# SAMV71_Xplained_Ultra_Memory.net
KiCad netlist of a schematic drawn in Altium Designer
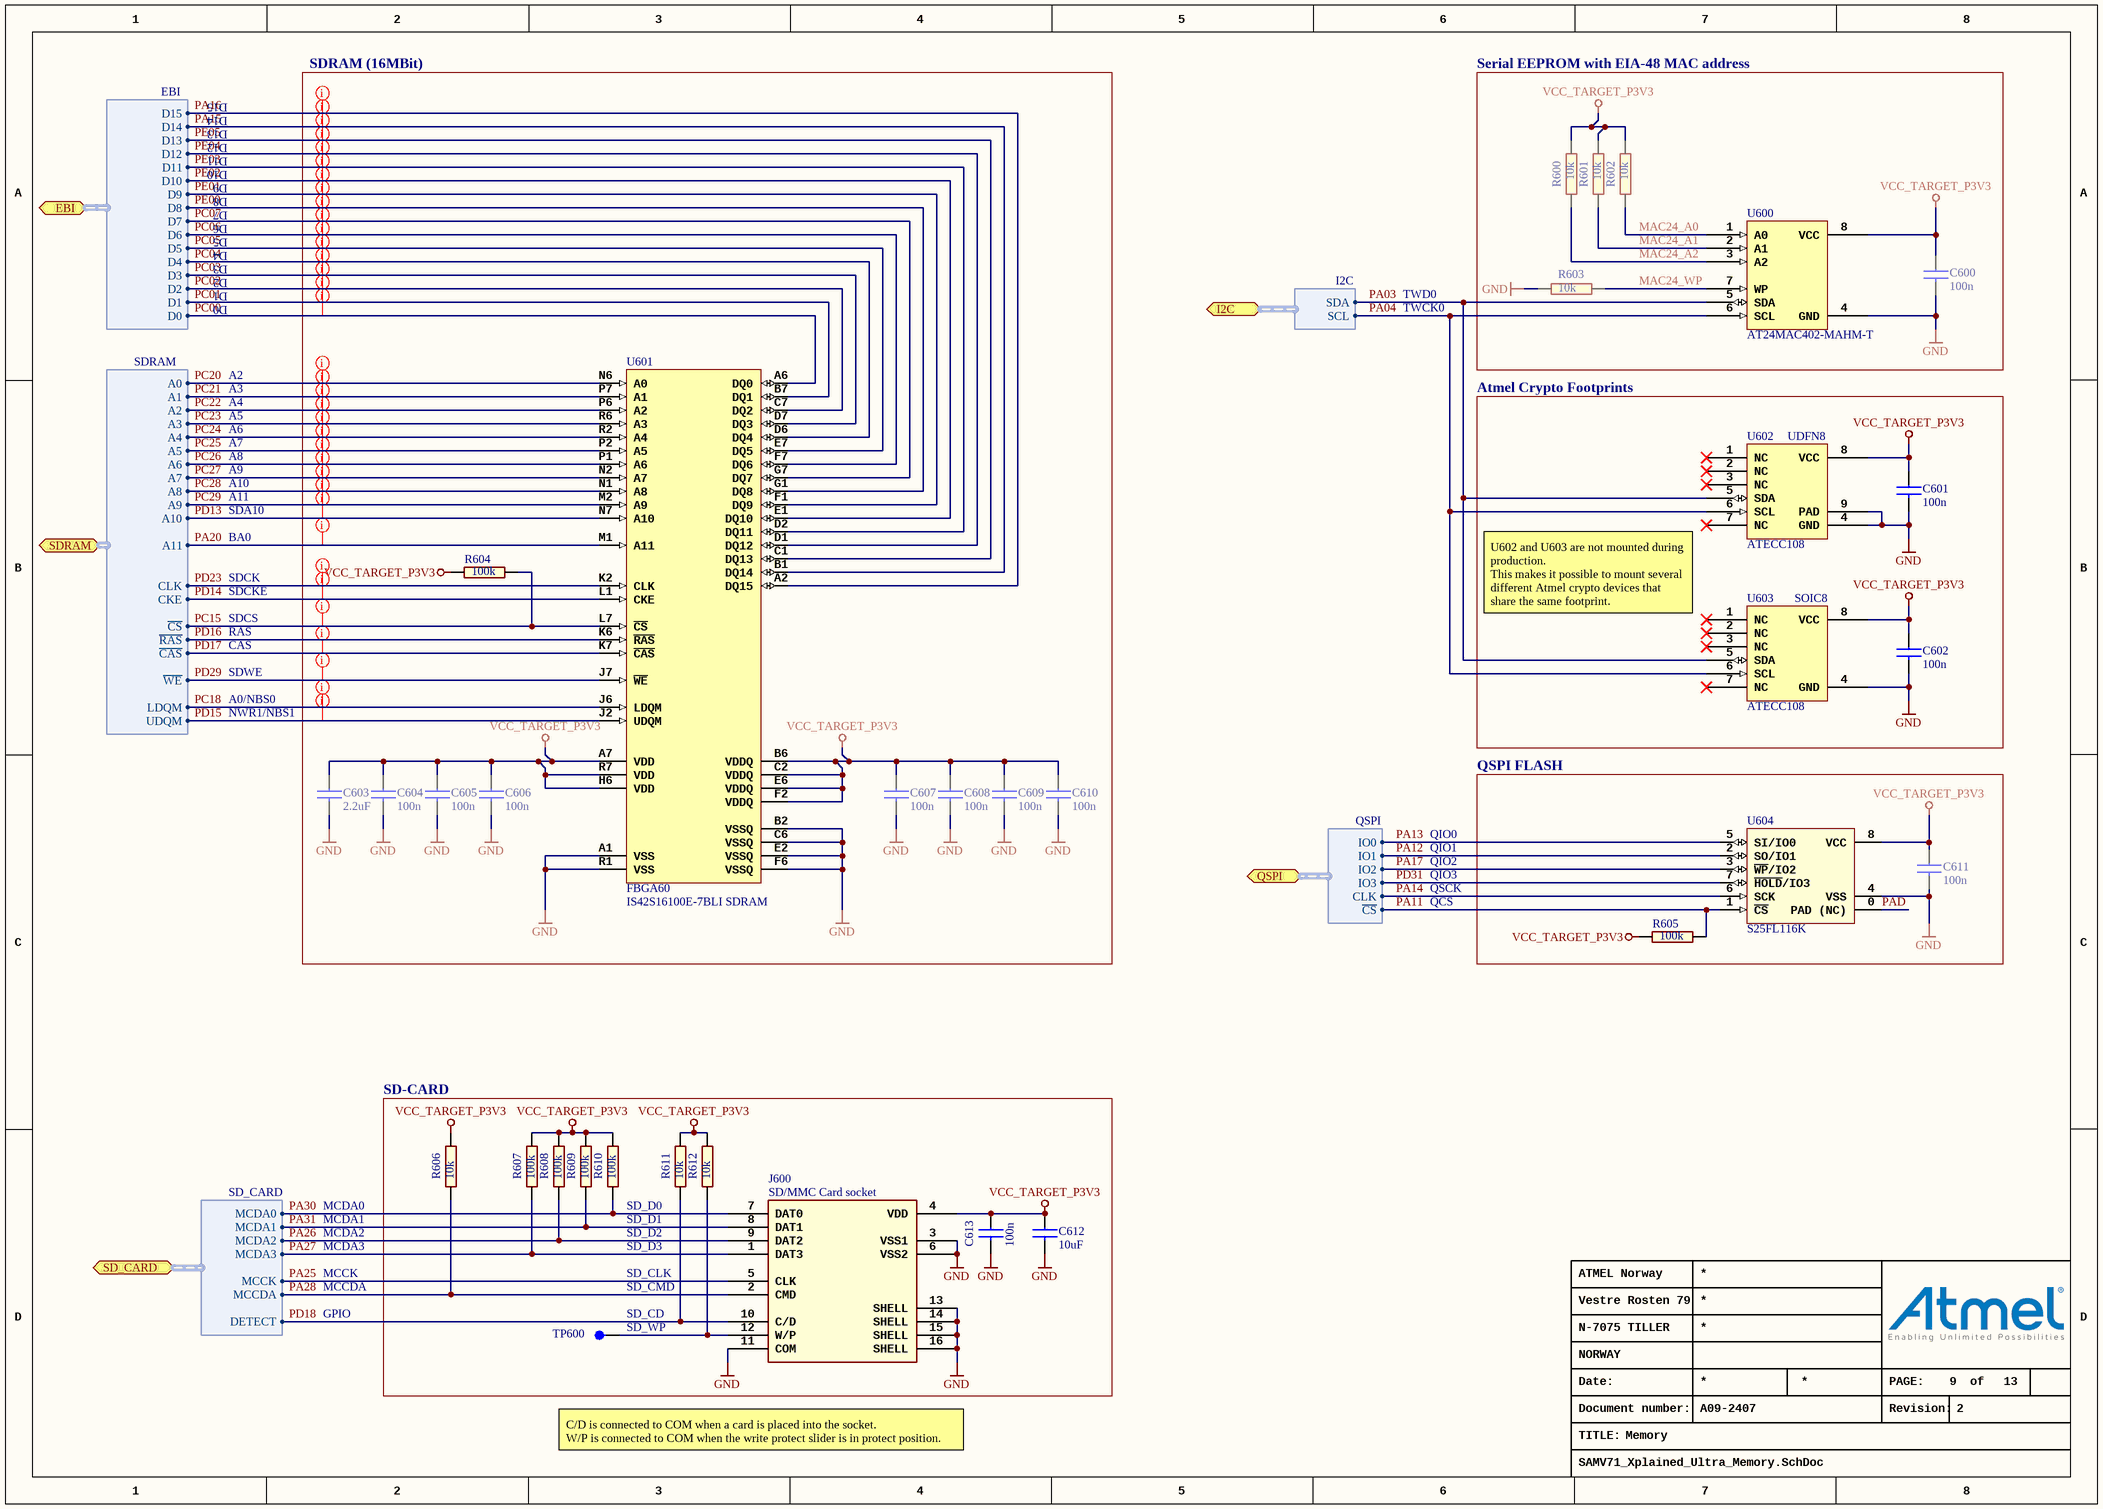
[diagram p0: SAMV71_Xplained_Ultra_Memory.SchDoc]

(export (version "E")
  (design (tool "Eeschema 10.0.6"))
  (components
    (comp (ref "C600")
      (value "100n")
      (footprint "AP1-00001")
      (description "Ceramic capacitor, SMD 0402, X7R, 16V, +/-10%")
      (fields (field (name "TOLERANCE") "16V, +/-10%") (field (name "MANUFACTURER") "Kemet"))
      (libsource (lib "AltiumDbLib") (part "CAP-NONPOL"))
    )
    (comp (ref "C601")
      (value "100n")
      (footprint "AP1-00001")
      (description "Ceramic capacitor, SMD 0402, X7R, 16V, +/-10%")
      (fields (field (name "TOLERANCE") "16V, +/-10%") (field (name "MANUFACTURER") "Kemet"))
      (libsource (lib "AltiumDbLib") (part "CAP-NONPOL"))
    )
    (comp (ref "C602")
      (value "100n")
      (footprint "AP1-00001")
      (description "Ceramic capacitor, SMD 0402, X7R, 16V, +/-10%")
      (fields (field (name "TOLERANCE") "16V, +/-10%") (field (name "MANUFACTURER") "Kemet"))
      (libsource (lib "AltiumDbLib") (part "CAP-NONPOL"))
    )
    (comp (ref "C603")
      (value "2.2uF")
      (footprint "AP1-00053")
      (description "Ceramic capacitor, SMD 0402, X5R, 6.3V, +/-20%")
      (fields (field (name "TOLERANCE") "Â±20%") (field (name "MANUFACTURER") "Kemet"))
      (libsource (lib "AltiumDbLib") (part "CAP-NONPOL"))
    )
    (comp (ref "C604")
      (value "100n")
      (footprint "AP1-00053")
      (description "Ceramic capacitor, SMD 0402, X7R, 16V, +/-10%")
      (fields (field (name "TOLERANCE") "16V, +/-10%") (field (name "MANUFACTURER") "Kemet"))
      (libsource (lib "AltiumDbLib") (part "CAP-NONPOL"))
    )
    (comp (ref "C605")
      (value "100n")
      (footprint "AP1-00053")
      (description "Ceramic capacitor, SMD 0402, X7R, 16V, +/-10%")
      (fields (field (name "TOLERANCE") "16V, +/-10%") (field (name "MANUFACTURER") "Kemet"))
      (libsource (lib "AltiumDbLib") (part "CAP-NONPOL"))
    )
    (comp (ref "C606")
      (value "100n")
      (footprint "AP1-00053")
      (description "Ceramic capacitor, SMD 0402, X7R, 16V, +/-10%")
      (fields (field (name "TOLERANCE") "16V, +/-10%") (field (name "MANUFACTURER") "Kemet"))
      (libsource (lib "AltiumDbLib") (part "CAP-NONPOL"))
    )
    (comp (ref "C607")
      (value "100n")
      (footprint "AP1-00053")
      (description "Ceramic capacitor, SMD 0402, X7R, 16V, +/-10%")
      (fields (field (name "TOLERANCE") "16V, +/-10%") (field (name "MANUFACTURER") "Kemet"))
      (libsource (lib "AltiumDbLib") (part "CAP-NONPOL"))
    )
    (comp (ref "C608")
      (value "100n")
      (footprint "AP1-00053")
      (description "Ceramic capacitor, SMD 0402, X7R, 16V, +/-10%")
      (fields (field (name "TOLERANCE") "16V, +/-10%") (field (name "MANUFACTURER") "Kemet"))
      (libsource (lib "AltiumDbLib") (part "CAP-NONPOL"))
    )
    (comp (ref "C609")
      (value "100n")
      (footprint "AP1-00053")
      (description "Ceramic capacitor, SMD 0402, X7R, 16V, +/-10%")
      (fields (field (name "TOLERANCE") "16V, +/-10%") (field (name "MANUFACTURER") "Kemet"))
      (libsource (lib "AltiumDbLib") (part "CAP-NONPOL"))
    )
    (comp (ref "C610")
      (value "100n")
      (footprint "AP1-00053")
      (description "Ceramic capacitor, SMD 0402, X7R, 16V, +/-10%")
      (fields (field (name "TOLERANCE") "16V, +/-10%") (field (name "MANUFACTURER") "Kemet"))
      (libsource (lib "AltiumDbLib") (part "CAP-NONPOL"))
    )
    (comp (ref "C611")
      (value "100n")
      (footprint "AP1-00001")
      (description "Ceramic capacitor, SMD 0402, X7R, 16V, +/-10%")
      (fields (field (name "TOLERANCE") "16V, +/-10%") (field (name "MANUFACTURER") "Kemet"))
      (libsource (lib "AltiumDbLib") (part "CAP-NONPOL"))
    )
    (comp (ref "C612")
      (value "10uF")
      (footprint "AP1-00041")
      (description "Ceramic capacitor, SMD 0805, X5R, 10V, 10 %, (de19441)")
      (fields (field (name "TOLERANCE") "10%") (field (name "MANUFACTURER") "Murata"))
      (libsource (lib "AltiumDbLib") (part "CAP-NONPOL"))
    )
    (comp (ref "C613")
      (value "100n")
      (footprint "AP1-00001")
      (description "Ceramic capacitor, SMD 0402, X7R, 16V, +/-10%")
      (fields (field (name "TOLERANCE") "16V, +/-10%") (field (name "MANUFACTURER") "Kemet"))
      (libsource (lib "AltiumDbLib") (part "CAP-NONPOL"))
    )
    (comp (ref "J600")
      (value "SD/MMC Card socket")
      (footprint "AP8-00377")
      (description "SD/MMC socket, 2.7mm, push-push, SMD")
      (fields
        (field (name "MANUFACTURER") "Kyocera-elco")
        (field (name "MPN") "KYOCERA - 14 5738 009 220 859+")
      )
      (libsource (lib "AltiumDbLib") (part "SD_MMC"))
    )
    (comp (ref "R600")
      (value "10k")
      (footprint "AP2-00000")
      (description "Thick film resistor, SMD 0402, 1/16W, 1%")
      (fields (field (name "TOLERANCE") "1 %") (field (name "MANUFACTURER") "vishay"))
      (libsource (lib "AltiumDbLib") (part "R2"))
    )
    (comp (ref "R601")
      (value "10k")
      (footprint "AP2-00000")
      (description "Thick film resistor, SMD 0402, 1/16W, 1%")
      (fields (field (name "TOLERANCE") "1 %") (field (name "MANUFACTURER") "vishay"))
      (libsource (lib "AltiumDbLib") (part "R2"))
    )
    (comp (ref "R602")
      (value "10k")
      (footprint "AP2-00000")
      (description "Thick film resistor, SMD 0402, 1/16W, 1%")
      (fields (field (name "TOLERANCE") "1 %") (field (name "MANUFACTURER") "vishay"))
      (libsource (lib "AltiumDbLib") (part "R2"))
    )
    (comp (ref "R603")
      (value "10k")
      (footprint "AP2-00000")
      (description "Thick film resistor, SMD 0402, 1/16W, 1%")
      (fields (field (name "TOLERANCE") "1 %") (field (name "MANUFACTURER") "vishay"))
      (libsource (lib "") (part "R2_1"))
    )
    (comp (ref "R604")
      (value "100k")
      (footprint "AP2-00000")
      (description "Thick film resistor, SMD 0402, 1/16W, 1%")
      (fields (field (name "TOLERANCE") "1 %") (field (name "Comment") "R2"))
      (libsource (lib "") (part "R2_1"))
    )
    (comp (ref "R605")
      (value "100k")
      (footprint "AP2-00000")
      (description "Thick film resistor, SMD 0402, 1/16W, 1%")
      (fields (field (name "TOLERANCE") "1 %") (field (name "Comment") "R2"))
      (libsource (lib "") (part "R2_1"))
    )
    (comp (ref "R606")
      (value "10k")
      (footprint "AP2-00000")
      (description "Thick film resistor, SMD 0402, 1/16W, 1%")
      (fields (field (name "TOLERANCE") "1 %") (field (name "Comment") "R2"))
      (libsource (lib "AltiumDbLib") (part "R2"))
    )
    (comp (ref "R607")
      (value "100k")
      (footprint "AP2-00000")
      (description "Thick film resistor, SMD 0402, 1/16W, 1%")
      (fields (field (name "TOLERANCE") "1 %") (field (name "Comment") "R2"))
      (libsource (lib "AltiumDbLib") (part "R2"))
    )
    (comp (ref "R608")
      (value "100k")
      (footprint "AP2-00000")
      (description "Thick film resistor, SMD 0402, 1/16W, 1%")
      (fields (field (name "TOLERANCE") "1 %") (field (name "Comment") "R2"))
      (libsource (lib "AltiumDbLib") (part "R2"))
    )
    (comp (ref "R609")
      (value "100k")
      (footprint "AP2-00000")
      (description "Thick film resistor, SMD 0402, 1/16W, 1%")
      (fields (field (name "TOLERANCE") "1 %") (field (name "Comment") "R2"))
      (libsource (lib "AltiumDbLib") (part "R2"))
    )
    (comp (ref "R610")
      (value "100k")
      (footprint "AP2-00000")
      (description "Thick film resistor, SMD 0402, 1/16W, 1%")
      (fields (field (name "TOLERANCE") "1 %") (field (name "Comment") "R2"))
      (libsource (lib "AltiumDbLib") (part "R2"))
    )
    (comp (ref "R611")
      (value "10k")
      (footprint "AP2-00000")
      (description "Thick film resistor, SMD 0402, 1/16W, 1%")
      (fields (field (name "TOLERANCE") "1 %") (field (name "Comment") "R2"))
      (libsource (lib "AltiumDbLib") (part "R2"))
    )
    (comp (ref "R612")
      (value "10k")
      (footprint "AP2-00000")
      (description "Thick film resistor, SMD 0402, 1/16W, 1%")
      (fields (field (name "TOLERANCE") "1 %") (field (name "Comment") "R2"))
      (libsource (lib "AltiumDbLib") (part "R2"))
    )
    (comp (ref "TP600")
      (value "TESTPOINT")
      (footprint "AP8-00010")
      (description "Single SMD testpad")
      (libsource (lib "AltiumDbLib") (part "TESTPOINT"))
    )
    (comp (ref "U600")
      (value "AT24MAC402-MAHM-T")
      (footprint "AP6-00186")
      (description "2kbit I2C EEPROM, single EUI-48 MAC, 1.7-5.5V, 2x3mm UDFN (8MA2)")
      (fields (field (name "Comment") "AT24MAC-8PIN"))
      (libsource (lib "AltiumDbLib") (part "AT24MAC-8PIN"))
    )
    (comp (ref "U601")
      (value "FBGA60")
      (footprint "AP6-00400")
      (description "16Mbit  SDRAM (512K Words x 16 Bits x 2 Banks), 143 MHz 3,3V")
      (fields (field (name "ALTIUM_VALUE") "IS42S16100E-7BLI SDRAM"))
      (libsource (lib "AltiumDbLib") (part "IS42S16100E"))
    )
    (comp (ref "U602")
      (value "ATECC108")
      (footprint "AP6-00409")
      (description "Secure authentication and product validation device, EEPROM, I2C, 2.0 - 5.5V, UDFN8")
      (libsource (lib "AltiumDbLib") (part "ATECC108_UDFN"))
    )
    (comp (ref "U603")
      (value "ATECC108")
      (footprint "AP6-00071")
      (description "Secure authentication and product validation device, EEPROM, I2C, 2.0 - 5.5V, SOIC8")
      (libsource (lib "AltiumDbLib") (part "ATECC108_SOIC"))
    )
    (comp (ref "U604")
      (value "S25FL116K")
      (footprint "AP6-00402")
      (description "16 Mbit (2MB) SPI Quad I/O flash, 3.3V, 108MHz, WSON-8, industrial temperature")
      (fields (field (name "Comment") "Also available as 32- and 64-Mbit."))
      (libsource (lib "AltiumDbLib") (part "S25FL1"))
    )
  )
  (nets
    (net (code "6") (name "/MAC24_A0") (class "Default")
      (node (ref "R602") (pin "1") (pinfunction "1_1") (pintype "passive"))
      (node (ref "U600") (pin "1") (pinfunction "A0_1") (pintype "input"))
    )
    (net (code "7") (name "/MAC24_A1") (class "Default")
      (node (ref "R601") (pin "1") (pinfunction "1_1") (pintype "passive"))
      (node (ref "U600") (pin "2") (pinfunction "A1_2") (pintype "input"))
    )
    (net (code "8") (name "/MAC24_A2") (class "Default")
      (node (ref "R600") (pin "1") (pinfunction "1_1") (pintype "passive"))
      (node (ref "U600") (pin "3") (pinfunction "A2_3") (pintype "input"))
    )
    (net (code "9") (name "/MAC24_WP") (class "Default")
      (node (ref "R603") (pin "2") (pinfunction "2_2") (pintype "passive"))
      (node (ref "U600") (pin "7") (pinfunction "WP_7") (pintype "input"))
    )
    (net (code "10") (name "/PA03") (class "Default")
      (node (ref "U600") (pin "5") (pinfunction "SDA_5") (pintype "bidirectional"))
      (node (ref "U602") (pin "5") (pinfunction "SDA_5") (pintype "bidirectional"))
      (node (ref "U603") (pin "5") (pinfunction "SDA_5") (pintype "bidirectional"))
    )
    (net (code "11") (name "/PA04") (class "Default")
      (node (ref "U600") (pin "6") (pinfunction "SCL_6") (pintype "input"))
      (node (ref "U602") (pin "6") (pinfunction "SCL_6") (pintype "input"))
      (node (ref "U603") (pin "6") (pinfunction "SCL_6") (pintype "input"))
    )
    (net (code "12") (name "/PA11") (class "Default")
      (node (ref "R605") (pin "2") (pinfunction "2_2") (pintype "passive"))
      (node (ref "U604") (pin "1") (pinfunction "~{CS}_1") (pintype "input"))
    )
    (net (code "13") (name "/PA12") (class "Default")
      (node (ref "U604") (pin "2") (pinfunction "SO/IO1_2") (pintype "bidirectional"))
    )
    (net (code "14") (name "/PA13") (class "Default")
      (node (ref "U604") (pin "5") (pinfunction "SI/IO0_5") (pintype "bidirectional"))
    )
    (net (code "15") (name "/PA14") (class "Default")
      (node (ref "U604") (pin "6") (pinfunction "SCK_6") (pintype "input"))
    )
    (net (code "16") (name "/PA15") (class "Default")
      (node (ref "U601") (pin "B1") (pinfunction "DQ14_B1") (pintype "bidirectional"))
    )
    (net (code "17") (name "/PA16") (class "Default")
      (node (ref "U601") (pin "A2") (pinfunction "DQ15_A2") (pintype "bidirectional"))
    )
    (net (code "18") (name "/PA17") (class "Default")
      (node (ref "U604") (pin "3") (pinfunction "~{WP}/IO2_3") (pintype "bidirectional"))
    )
    (net (code "19") (name "/PA20") (class "Default")
      (node (ref "U601") (pin "M1") (pinfunction "A11_M1") (pintype "input"))
    )
    (net (code "20") (name "/PA25") (class "Default")
      (node (ref "J600") (pin "5") (pinfunction "CLK_5") (pintype "passive"))
    )
    (net (code "21") (name "/PA26") (class "Default")
      (node (ref "J600") (pin "9") (pinfunction "DAT2_9") (pintype "passive"))
      (node (ref "R608") (pin "1") (pinfunction "1_1") (pintype "passive"))
    )
    (net (code "22") (name "/PA27") (class "Default")
      (node (ref "J600") (pin "1") (pinfunction "DAT3_1") (pintype "passive"))
      (node (ref "R607") (pin "1") (pinfunction "1_1") (pintype "passive"))
    )
    (net (code "23") (name "/PA28") (class "Default")
      (node (ref "J600") (pin "2") (pinfunction "CMD_2") (pintype "passive"))
      (node (ref "R606") (pin "1") (pinfunction "1_1") (pintype "passive"))
    )
    (net (code "24") (name "/PA30") (class "Default")
      (node (ref "J600") (pin "7") (pinfunction "DAT0_7") (pintype "passive"))
      (node (ref "R610") (pin "1") (pinfunction "1_1") (pintype "passive"))
    )
    (net (code "25") (name "/PA31") (class "Default")
      (node (ref "J600") (pin "8") (pinfunction "DAT1_8") (pintype "passive"))
      (node (ref "R609") (pin "1") (pinfunction "1_1") (pintype "passive"))
    )
    (net (code "26") (name "/PAD") (class "Default")
      (node (ref "U604") (pin "0") (pinfunction "PAD_(NC)_0") (pintype "power_in"))
    )
    (net (code "27") (name "/PC00") (class "Default")
      (node (ref "U601") (pin "A6") (pinfunction "DQ0_A6") (pintype "bidirectional"))
    )
    (net (code "28") (name "/PC01") (class "Default")
      (node (ref "U601") (pin "B7") (pinfunction "DQ1_B7") (pintype "bidirectional"))
    )
    (net (code "29") (name "/PC02") (class "Default")
      (node (ref "U601") (pin "C7") (pinfunction "DQ2_C7") (pintype "bidirectional"))
    )
    (net (code "30") (name "/PC03") (class "Default")
      (node (ref "U601") (pin "D7") (pinfunction "DQ3_D7") (pintype "bidirectional"))
    )
    (net (code "31") (name "/PC04") (class "Default")
      (node (ref "U601") (pin "D6") (pinfunction "DQ4_D6") (pintype "bidirectional"))
    )
    (net (code "32") (name "/PC05") (class "Default")
      (node (ref "U601") (pin "E7") (pinfunction "DQ5_E7") (pintype "bidirectional"))
    )
    (net (code "33") (name "/PC06") (class "Default")
      (node (ref "U601") (pin "F7") (pinfunction "DQ6_F7") (pintype "bidirectional"))
    )
    (net (code "34") (name "/PC07") (class "Default")
      (node (ref "U601") (pin "G7") (pinfunction "DQ7_G7") (pintype "bidirectional"))
    )
    (net (code "35") (name "/PC15") (class "Default")
      (node (ref "R604") (pin "2") (pinfunction "2_2") (pintype "passive"))
      (node (ref "U601") (pin "L7") (pinfunction "~{CS}_L7") (pintype "input"))
    )
    (net (code "36") (name "/PC18") (class "Default")
      (node (ref "U601") (pin "J6") (pinfunction "LDQM_J6") (pintype "input"))
    )
    (net (code "37") (name "/PC20") (class "Default")
      (node (ref "U601") (pin "N6") (pinfunction "A0_N6") (pintype "input"))
    )
    (net (code "38") (name "/PC21") (class "Default")
      (node (ref "U601") (pin "P7") (pinfunction "A1_P7") (pintype "input"))
    )
    (net (code "39") (name "/PC22") (class "Default")
      (node (ref "U601") (pin "P6") (pinfunction "A2_P6") (pintype "input"))
    )
    (net (code "40") (name "/PC23") (class "Default")
      (node (ref "U601") (pin "R6") (pinfunction "A3_R6") (pintype "input"))
    )
    (net (code "41") (name "/PC24") (class "Default")
      (node (ref "U601") (pin "R2") (pinfunction "A4_R2") (pintype "input"))
    )
    (net (code "42") (name "/PC25") (class "Default")
      (node (ref "U601") (pin "P2") (pinfunction "A5_P2") (pintype "input"))
    )
    (net (code "43") (name "/PC26") (class "Default")
      (node (ref "U601") (pin "P1") (pinfunction "A6_P1") (pintype "input"))
    )
    (net (code "44") (name "/PC27") (class "Default")
      (node (ref "U601") (pin "N2") (pinfunction "A7_N2") (pintype "input"))
    )
    (net (code "45") (name "/PC28") (class "Default")
      (node (ref "U601") (pin "N1") (pinfunction "A8_N1") (pintype "input"))
    )
    (net (code "46") (name "/PC29") (class "Default")
      (node (ref "U601") (pin "M2") (pinfunction "A9_M2") (pintype "input"))
    )
    (net (code "47") (name "/PD13") (class "Default")
      (node (ref "U601") (pin "N7") (pinfunction "A10_N7") (pintype "input"))
    )
    (net (code "48") (name "/PD14") (class "Default")
      (node (ref "U601") (pin "L1") (pinfunction "CKE_L1") (pintype "input"))
    )
    (net (code "49") (name "/PD15") (class "Default")
      (node (ref "U601") (pin "J2") (pinfunction "UDQM_J2") (pintype "input"))
    )
    (net (code "50") (name "/PD16") (class "Default")
      (node (ref "U601") (pin "K6") (pinfunction "~{RAS}_K6") (pintype "input"))
    )
    (net (code "51") (name "/PD17") (class "Default")
      (node (ref "U601") (pin "K7") (pinfunction "~{CAS}_K7") (pintype "input"))
    )
    (net (code "52") (name "/PD18") (class "Default")
      (node (ref "J600") (pin "10") (pinfunction "C/D_10") (pintype "passive"))
      (node (ref "R611") (pin "1") (pinfunction "1_1") (pintype "passive"))
    )
    (net (code "53") (name "/PD23") (class "Default")
      (node (ref "U601") (pin "K2") (pinfunction "CLK_K2") (pintype "input"))
    )
    (net (code "54") (name "/PD29") (class "Default")
      (node (ref "U601") (pin "J7") (pinfunction "~{WE}_J7") (pintype "input"))
    )
    (net (code "55") (name "/PD31") (class "Default")
      (node (ref "U604") (pin "7") (pinfunction "~{HOLD}/IO3_7") (pintype "bidirectional"))
    )
    (net (code "56") (name "/PE00") (class "Default")
      (node (ref "U601") (pin "G1") (pinfunction "DQ8_G1") (pintype "bidirectional"))
    )
    (net (code "57") (name "/PE01") (class "Default")
      (node (ref "U601") (pin "F1") (pinfunction "DQ9_F1") (pintype "bidirectional"))
    )
    (net (code "58") (name "/PE02") (class "Default")
      (node (ref "U601") (pin "E1") (pinfunction "DQ10_E1") (pintype "bidirectional"))
    )
    (net (code "59") (name "/PE03") (class "Default")
      (node (ref "U601") (pin "D2") (pinfunction "DQ11_D2") (pintype "bidirectional"))
    )
    (net (code "60") (name "/PE04") (class "Default")
      (node (ref "U601") (pin "D1") (pinfunction "DQ12_D1") (pintype "bidirectional"))
    )
    (net (code "61") (name "/PE05") (class "Default")
      (node (ref "U601") (pin "C1") (pinfunction "DQ13_C1") (pintype "bidirectional"))
    )
    (net (code "67") (name "GND") (class "Default")
      (node (ref "C600") (pin "2") (pinfunction "2_2") (pintype "passive"))
      (node (ref "C601") (pin "2") (pinfunction "2_2") (pintype "passive"))
      (node (ref "C602") (pin "2") (pinfunction "2_2") (pintype "passive"))
      (node (ref "C603") (pin "2") (pinfunction "2_2") (pintype "passive"))
      (node (ref "C604") (pin "2") (pinfunction "2_2") (pintype "passive"))
      (node (ref "C605") (pin "2") (pinfunction "2_2") (pintype "passive"))
      (node (ref "C606") (pin "2") (pinfunction "2_2") (pintype "passive"))
      (node (ref "C607") (pin "2") (pinfunction "2_2") (pintype "passive"))
      (node (ref "C608") (pin "2") (pinfunction "2_2") (pintype "passive"))
      (node (ref "C609") (pin "2") (pinfunction "2_2") (pintype "passive"))
      (node (ref "C610") (pin "2") (pinfunction "2_2") (pintype "passive"))
      (node (ref "C611") (pin "2") (pinfunction "2_2") (pintype "passive"))
      (node (ref "C612") (pin "2") (pinfunction "2_2") (pintype "passive"))
      (node (ref "C613") (pin "2") (pinfunction "2_2") (pintype "passive"))
      (node (ref "J600") (pin "11") (pinfunction "COM_11") (pintype "passive"))
      (node (ref "J600") (pin "13") (pinfunction "SHELL_13") (pintype "passive"))
      (node (ref "J600") (pin "14") (pinfunction "SHELL_14") (pintype "passive"))
      (node (ref "J600") (pin "15") (pinfunction "SHELL_15") (pintype "passive"))
      (node (ref "J600") (pin "16") (pinfunction "SHELL_16") (pintype "passive"))
      (node (ref "J600") (pin "3") (pinfunction "VSS1_3") (pintype "passive"))
      (node (ref "J600") (pin "6") (pinfunction "VSS2_6") (pintype "passive"))
      (node (ref "R603") (pin "1") (pinfunction "1_1") (pintype "passive"))
      (node (ref "U600") (pin "4") (pinfunction "GND_4") (pintype "power_in"))
      (node (ref "U601") (pin "A1") (pinfunction "VSS_A1") (pintype "power_in"))
      (node (ref "U601") (pin "B2") (pinfunction "VSSQ_B2") (pintype "power_in"))
      (node (ref "U601") (pin "C6") (pinfunction "VSSQ_C6") (pintype "power_in"))
      (node (ref "U601") (pin "E2") (pinfunction "VSSQ_E2") (pintype "power_in"))
      (node (ref "U601") (pin "F6") (pinfunction "VSSQ_F6") (pintype "power_in"))
      (node (ref "U601") (pin "R1") (pinfunction "VSS_R1") (pintype "power_in"))
      (node (ref "U602") (pin "4") (pinfunction "GND_4") (pintype "power_in"))
      (node (ref "U602") (pin "9") (pinfunction "PAD_9") (pintype "power_in"))
      (node (ref "U603") (pin "4") (pinfunction "GND_4") (pintype "power_in"))
      (node (ref "U604") (pin "4") (pinfunction "VSS_4") (pintype "power_in"))
    )
    (net (code "68") (name "Net-(J600-W{slash}P)") (class "Default")
      (node (ref "J600") (pin "12") (pinfunction "W/P_12") (pintype "passive"))
      (node (ref "R612") (pin "1") (pinfunction "1_1") (pintype "passive"))
      (node (ref "TP600") (pin "1") (pinfunction "1_1") (pintype "passive"))
    )
    (net (code "69") (name "VCC_TARGET_P3V3") (class "Default")
      (node (ref "C600") (pin "1") (pinfunction "1_1") (pintype "passive"))
      (node (ref "C601") (pin "1") (pinfunction "1_1") (pintype "passive"))
      (node (ref "C602") (pin "1") (pinfunction "1_1") (pintype "passive"))
      (node (ref "C603") (pin "1") (pinfunction "1_1") (pintype "passive"))
      (node (ref "C604") (pin "1") (pinfunction "1_1") (pintype "passive"))
      (node (ref "C605") (pin "1") (pinfunction "1_1") (pintype "passive"))
      (node (ref "C606") (pin "1") (pinfunction "1_1") (pintype "passive"))
      (node (ref "C607") (pin "1") (pinfunction "1_1") (pintype "passive"))
      (node (ref "C608") (pin "1") (pinfunction "1_1") (pintype "passive"))
      (node (ref "C609") (pin "1") (pinfunction "1_1") (pintype "passive"))
      (node (ref "C610") (pin "1") (pinfunction "1_1") (pintype "passive"))
      (node (ref "C611") (pin "1") (pinfunction "1_1") (pintype "passive"))
      (node (ref "C612") (pin "1") (pinfunction "1_1") (pintype "passive"))
      (node (ref "C613") (pin "1") (pinfunction "1_1") (pintype "passive"))
      (node (ref "J600") (pin "4") (pinfunction "VDD_4") (pintype "passive"))
      (node (ref "R600") (pin "2") (pinfunction "2_2") (pintype "passive"))
      (node (ref "R601") (pin "2") (pinfunction "2_2") (pintype "passive"))
      (node (ref "R602") (pin "2") (pinfunction "2_2") (pintype "passive"))
      (node (ref "R604") (pin "1") (pinfunction "1_1") (pintype "passive"))
      (node (ref "R605") (pin "1") (pinfunction "1_1") (pintype "passive"))
      (node (ref "R606") (pin "2") (pinfunction "2_2") (pintype "passive"))
      (node (ref "R607") (pin "2") (pinfunction "2_2") (pintype "passive"))
      (node (ref "R608") (pin "2") (pinfunction "2_2") (pintype "passive"))
      (node (ref "R609") (pin "2") (pinfunction "2_2") (pintype "passive"))
      (node (ref "R610") (pin "2") (pinfunction "2_2") (pintype "passive"))
      (node (ref "R611") (pin "2") (pinfunction "2_2") (pintype "passive"))
      (node (ref "R612") (pin "2") (pinfunction "2_2") (pintype "passive"))
      (node (ref "U600") (pin "8") (pinfunction "VCC_8") (pintype "power_in"))
      (node (ref "U601") (pin "A7") (pinfunction "VDD_A7") (pintype "power_in"))
      (node (ref "U601") (pin "B6") (pinfunction "VDDQ_B6") (pintype "power_in"))
      (node (ref "U601") (pin "C2") (pinfunction "VDDQ_C2") (pintype "power_in"))
      (node (ref "U601") (pin "E6") (pinfunction "VDDQ_E6") (pintype "power_in"))
      (node (ref "U601") (pin "F2") (pinfunction "VDDQ_F2") (pintype "power_in"))
      (node (ref "U601") (pin "H6") (pinfunction "VDD_H6") (pintype "power_in"))
      (node (ref "U601") (pin "R7") (pinfunction "VDD_R7") (pintype "power_in"))
      (node (ref "U602") (pin "8") (pinfunction "VCC_8") (pintype "power_in"))
      (node (ref "U603") (pin "8") (pinfunction "VCC_8") (pintype "power_in"))
      (node (ref "U604") (pin "8") (pinfunction "VCC_8") (pintype "power_in"))
    )
    (net (code "70") (name "unconnected-(U602-NC-Pad1)") (class "Default")
      (node (ref "U602") (pin "1") (pinfunction "NC_1") (pintype "passive+no_connect"))
    )
    (net (code "71") (name "unconnected-(U602-NC-Pad2)") (class "Default")
      (node (ref "U602") (pin "2") (pinfunction "NC_2") (pintype "passive+no_connect"))
    )
    (net (code "72") (name "unconnected-(U602-NC-Pad3)") (class "Default")
      (node (ref "U602") (pin "3") (pinfunction "NC_3") (pintype "passive+no_connect"))
    )
    (net (code "73") (name "unconnected-(U602-NC-Pad7)") (class "Default")
      (node (ref "U602") (pin "7") (pinfunction "NC_7") (pintype "passive+no_connect"))
    )
    (net (code "74") (name "unconnected-(U603-NC-Pad1)") (class "Default")
      (node (ref "U603") (pin "1") (pinfunction "NC_1") (pintype "passive+no_connect"))
    )
    (net (code "75") (name "unconnected-(U603-NC-Pad2)") (class "Default")
      (node (ref "U603") (pin "2") (pinfunction "NC_2") (pintype "passive+no_connect"))
    )
    (net (code "76") (name "unconnected-(U603-NC-Pad3)") (class "Default")
      (node (ref "U603") (pin "3") (pinfunction "NC_3") (pintype "passive+no_connect"))
    )
    (net (code "77") (name "unconnected-(U603-NC-Pad7)") (class "Default")
      (node (ref "U603") (pin "7") (pinfunction "NC_7") (pintype "passive+no_connect"))
    )
  )
)
